# PSU.net
KiCad netlist of a schematic drawn in Altium Designer
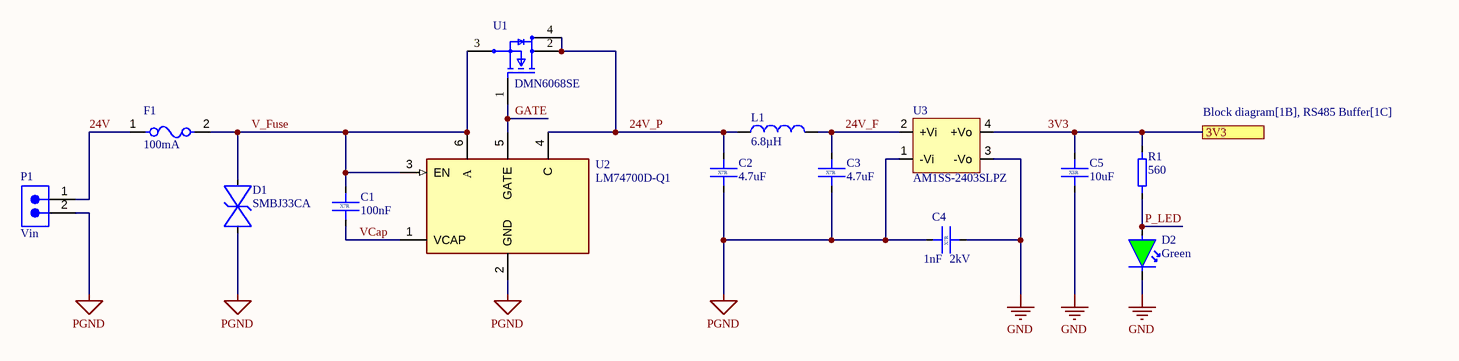
[diagram p0: PSU.SchDoc]

(export (version "E")
  (design (tool "Eeschema 10.0.6"))
  (components
    (comp (ref "C1")
      (value "100nF")
      (footprint "C0603-DC")
      (description "0603 100 nF 50 V ±5 % Tolerance X7R SMT MLCC")
      (fields
        (field (name "MANUFACTURER") "KYOCERA AVX")
        (field (name "MANUFACTURER PART NUMBER") "06035C104JAT2A")
        (field (name "DIELECTRIC") "X7R")
      )
      (libsource (lib "Cuatro-20 Library") (part "06035C104JAT2A"))
    )
    (comp (ref "C2")
      (value "4.7uF")
      (footprint "C1206-FB")
      (description "1206 4.7 uF 50 V ±10 % Tolerance X7R SMT MLCC")
      (fields
        (field (name "MANUFACTURER") "KYOCERA AVX")
        (field (name "MANUFACTURER PART NUMBER") "12065C475K4Z2A")
        (field (name "DIELECTRIC") "X7R")
      )
      (libsource (lib "Cuatro-20 Library") (part "12065C475K4Z2A"))
    )
    (comp (ref "C3")
      (value "4.7uF")
      (footprint "C1206-FB")
      (description "1206 4.7 uF 50 V ±10 % Tolerance X7R SMT MLCC")
      (fields
        (field (name "MANUFACTURER") "KYOCERA AVX")
        (field (name "MANUFACTURER PART NUMBER") "12065C475K4Z2A")
        (field (name "DIELECTRIC") "X7R")
      )
      (libsource (lib "Cuatro-20 Library") (part "12065C475K4Z2A"))
    )
    (comp (ref "C4")
      (value "1nF")
      (footprint "C1210-GB")
      (description "1210 1 nF 2 kV ±10 % Tolerance X7R SMT MLCC")
      (fields
        (field (name "MANUFACTURER") "Yageo Group")
        (field (name "MANUFACTURER PART NUMBER") "CC1206KKX7RDBB102")
        (field (name "VOLTAGE") "2kV")
        (field (name "DIELECTRIC") "X7R")
      )
      (libsource (lib "Cuatro-20 Library") (part "CC1206KKX7RDBB102"))
    )
    (comp (ref "C5")
      (value "10uF")
      (footprint "C0805-EA")
      (description "0805 10 uF 25 V ±10 % Tolerance X5R SMT MLCC")
      (fields
        (field (name "MANUFACTURER") "KYOCERA AVX")
        (field (name "MANUFACTURER PART NUMBER") "08053D106KAT2A")
        (field (name "DIELECTRIC") "X5R")
      )
      (libsource (lib "Cuatro-20 Library") (part "08053D106KAT2A"))
    )
    (comp (ref "D1")
      (value "SMBJ33CA")
      (footprint "SMB")
      (description "SMBJ33A Series 600 W 33 V Surface Mount Bi-Directional TVS Diode - DO-214AA")
      (fields (field (name "MANUFACTURER") "Littelfuse"))
      (libsource (lib "Cuatro-20 Library") (part "SMBJ33CA"))
    )
    (comp (ref "D2")
      (value "Green")
      (footprint "LED 0603 Green")
      (description "Single-color LEDs; LITEON; LTST-C190KGKT; Green; 130 °; 2.4 V; 0603")
      (fields
        (field (name "MANUFACTURER") "Vishay Lite-On")
        (field (name "MANUFACTURER PART NUMBER") "LTST-C190KGKT")
      )
      (libsource (lib "Cuatro-20 Library") (part "LTST-C190KGKT"))
    )
    (comp (ref "F1")
      (value "100mA")
      (footprint "FP-MF-MSMF010-MFG")
      (description "PTC Resettable Fuse 0.1A(hold) 0.3A(trip) 60V 40A 0.8W 1.5s 0.7Ohm SMD Solder Pad 1812 T/R")
      (fields (field (name "MANUFACTURER") "Bourns") (field (name "MANUFACTURER PART NUMBER") "MF-MSMF010-2"))
      (libsource (lib "Cuatro-20 Library") (part "MF-MSMF010-2"))
    )
    (comp (ref "L1")
      (value "6.8µH")
      (footprint "L0806-Murata")
      (description "Inductor Power Shielded Multi-Layer 6.8uH 20% 2MHz Ferrite 0.4A 0.52Ohm DCR 0805 T/R")
      (fields
        (field (name "MANUFACTURER") "TDK")
        (field (name "MANUFACTURER PART NUMBER") "MLZ2012M6R8WT000")
      )
      (libsource (lib "Cuatro-20 Library") (part "MLZ2012M6R8WT000"))
    )
    (comp (ref "P1")
      (value "Vin")
      (footprint "691313510002")
      (description "Strip Terminal Block, 20A, 1 Row(s), 1 Deck(s)")
      (fields (field (name "VOLTAGE") "300V") (field (name "MANUFACTURER") "Wurth Elektronik"))
      (libsource (lib "Cuatro-20 Library") (part "691313510002"))
    )
    (comp (ref "R1")
      (value "560")
      (footprint "RC0603")
      (description "0603 Res 560 Ω 5% 1/10W 75 V")
      (fields (field (name "TOLERANCE") "1%"))
      (libsource (lib "Cuatro-20 Library") (part "RC0603JR-07560R"))
    )
    (comp (ref "U1")
      (value "DMN6068SE")
      (footprint "SOT223")
      (description "N-Channel 60 V 68 mOhm Surface Mount Enhancement Mode Mosfet - SOT-223-3")
      (fields (field (name "MANUFACTURER") "Diodes") (field (name "MANUFACTURER PART NUMBER") "DMN6068SE-13"))
      (libsource (lib "Cuatro-20 Library") (part "DMN6068SE-13"))
    )
    (comp (ref "U2")
      (value "LM74700D-Q1")
      (footprint "SOT23-6-TI")
      (description "Power Supply Support Circuit, Fixed, 1 Channel, PDSO6")
      (fields
        (field (name "MANUFACTURER") "Texas Instrument")
        (field (name "MANUFACTURER PART NUMBER") "LM74700QDBVRQ1")
      )
      (libsource (lib "Cuatro-20 Library") (part "LM74700QDBVRQ1"))
    )
    (comp (ref "U3")
      (value "AM1SS-2403SLPZ")
      (footprint "AM1SS-LPZ")
      (description "DC-DC Unregulated Power Supply Module, 1 Output, 1W, Hybrid")
      (fields (field (name "MANUFACTURER") "Aimtec"))
      (libsource (lib "Cuatro-20 Library") (part "AM1SS-2403SLPZ"))
    )
  )
  (nets
    (net (code "1") (name "/3V3") (class "Default")
      (node (ref "C5") (pin "1") (pinfunction "1_1") (pintype "passive"))
      (node (ref "R1") (pin "2") (pinfunction "2_2") (pintype "passive"))
      (node (ref "U3") (pin "4") (pinfunction "+Vo_4") (pintype "power_in"))
    )
    (net (code "2") (name "/24V") (class "Default")
      (node (ref "F1") (pin "1") (pinfunction "1_1") (pintype "passive"))
      (node (ref "P1") (pin "1") (pinfunction "1_1") (pintype "passive"))
    )
    (net (code "3") (name "/24V_F") (class "Default")
      (node (ref "C3") (pin "1") (pinfunction "1_1") (pintype "passive"))
      (node (ref "L1") (pin "2") (pinfunction "2_2") (pintype "passive"))
      (node (ref "U3") (pin "2") (pinfunction "+Vi_2") (pintype "power_in"))
    )
    (net (code "4") (name "/24V_P") (class "Default")
      (node (ref "C2") (pin "1") (pinfunction "1_1") (pintype "passive"))
      (node (ref "L1") (pin "1") (pinfunction "1_1") (pintype "passive"))
      (node (ref "U1") (pin "2") (pinfunction "D_2") (pintype "passive"))
      (node (ref "U1") (pin "4") (pinfunction "D_4") (pintype "passive"))
      (node (ref "U2") (pin "4") (pinfunction "C_4") (pintype "passive"))
    )
    (net (code "5") (name "/GATE") (class "Default")
      (node (ref "U1") (pin "1") (pinfunction "G_1") (pintype "passive"))
      (node (ref "U2") (pin "5") (pinfunction "GATE_5") (pintype "passive"))
    )
    (net (code "6") (name "/P_LED") (class "Default")
      (node (ref "D2") (pin "2") (pinfunction "A_2") (pintype "passive"))
      (node (ref "R1") (pin "1") (pinfunction "1_1") (pintype "passive"))
    )
    (net (code "7") (name "/VCap") (class "Default")
      (node (ref "C1") (pin "2") (pinfunction "2_2") (pintype "passive"))
      (node (ref "U2") (pin "1") (pinfunction "VCAP_1") (pintype "power_in"))
    )
    (net (code "8") (name "/V_Fuse") (class "Default")
      (node (ref "C1") (pin "1") (pinfunction "1_1") (pintype "passive"))
      (node (ref "D1") (pin "2") (pinfunction "A_2") (pintype "passive"))
      (node (ref "F1") (pin "2") (pinfunction "2_2") (pintype "passive"))
      (node (ref "U1") (pin "3") (pinfunction "S_3") (pintype "passive"))
      (node (ref "U2") (pin "3") (pinfunction "EN_3") (pintype "input"))
      (node (ref "U2") (pin "6") (pinfunction "A_6") (pintype "passive"))
    )
    (net (code "9") (name "GND") (class "Default")
      (node (ref "C4") (pin "2") (pinfunction "2_2") (pintype "passive"))
      (node (ref "C5") (pin "2") (pinfunction "2_2") (pintype "passive"))
      (node (ref "D2") (pin "1") (pinfunction "C_1") (pintype "passive"))
      (node (ref "U3") (pin "3") (pinfunction "-Vo_3") (pintype "power_in"))
    )
    (net (code "10") (name "PGND") (class "Default")
      (node (ref "C2") (pin "2") (pinfunction "2_2") (pintype "passive"))
      (node (ref "C3") (pin "2") (pinfunction "2_2") (pintype "passive"))
      (node (ref "C4") (pin "1") (pinfunction "1_1") (pintype "passive"))
      (node (ref "D1") (pin "1") (pinfunction "C_1") (pintype "passive"))
      (node (ref "P1") (pin "2") (pinfunction "2_2") (pintype "passive"))
      (node (ref "U2") (pin "2") (pinfunction "GND_2") (pintype "power_in"))
      (node (ref "U3") (pin "1") (pinfunction "-Vi_1") (pintype "power_in"))
    )
  )
)
